# pierce-test-board.net
KiCad netlist of a schematic drawn in EAGLE
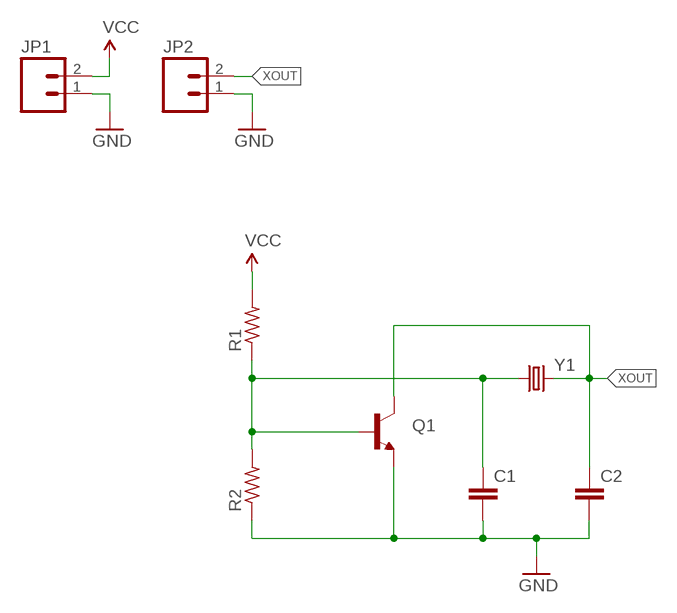
[diagram p0: schematic, sheet 1]

(export (version "E")
  (design (tool "Eeschema 10.0.6"))
  (components
    (comp (ref "C1")
      (value "CAPACITOR-CERAMIC025-024X044")
      (footprint "eagle-import:C025-024X044")
      (libsource (lib "eagle-import") (part "CAPACITOR-CERAMIC025-024X044"))
    )
    (comp (ref "C2")
      (value "CAPACITOR-CERAMIC025-024X044")
      (footprint "eagle-import:C025-024X044")
      (libsource (lib "eagle-import") (part "CAPACITOR-CERAMIC025-024X044"))
    )
    (comp (ref "JP1")
      (value "M02PTH")
      (footprint "eagle-import:1X02")
      (libsource (lib "eagle-import") (part "M02PTH"))
    )
    (comp (ref "JP2")
      (value "M02PTH")
      (footprint "eagle-import:1X02")
      (libsource (lib "eagle-import") (part "M02PTH"))
    )
    (comp (ref "Q1")
      (value "TRANSISTOR_NPNTO-92-AMMO-EBC")
      (footprint "eagle-import:TO-92-AMMO")
      (libsource (lib "eagle-import") (part "TRANSISTOR_NPNTO-92-AMMO-EBC"))
    )
    (comp (ref "R1")
      (value "RESISTORPTH-AXIAL-5.08MM")
      (footprint "eagle-import:RESISTOR-AXIAL-PTH-5.08MM")
      (libsource (lib "eagle-import") (part "RESISTORPTH-AXIAL-5.08MM"))
    )
    (comp (ref "R2")
      (value "RESISTORPTH-AXIAL-5.08MM")
      (footprint "eagle-import:RESISTOR-AXIAL-PTH-5.08MM")
      (libsource (lib "eagle-import") (part "RESISTORPTH-AXIAL-5.08MM"))
    )
    (comp (ref "Y1")
      (value "CRYSTALHC49UV")
      (footprint "eagle-import:HC49U-V")
      (libsource (lib "eagle-import") (part "CRYSTALHC49UV"))
    )
  )
  (nets
    (net (code "1") (name "GND") (class "Default")
      (node (ref "C1") (pin "2") (pinfunction "2_2") (pintype "passive"))
      (node (ref "C2") (pin "2") (pinfunction "2_2") (pintype "passive"))
      (node (ref "JP1") (pin "1") (pinfunction "1_1") (pintype "passive"))
      (node (ref "JP2") (pin "1") (pinfunction "1_1") (pintype "passive"))
      (node (ref "Q1") (pin "1") (pinfunction "E_1") (pintype "passive"))
      (node (ref "R2") (pin "P$1") (pinfunction "1_P$1") (pintype "passive"))
    )
    (net (code "2") (name "Net-(Q1-B)") (class "Default")
      (node (ref "C1") (pin "1") (pinfunction "1_1") (pintype "passive"))
      (node (ref "Q1") (pin "2") (pinfunction "B_2") (pintype "passive"))
      (node (ref "R1") (pin "P$1") (pinfunction "1_P$1") (pintype "passive"))
      (node (ref "R2") (pin "P$2") (pinfunction "2_P$2") (pintype "passive"))
      (node (ref "Y1") (pin "1") (pinfunction "1_1") (pintype "passive"))
    )
    (net (code "3") (name "VCC") (class "Default")
      (node (ref "JP1") (pin "2") (pinfunction "2_2") (pintype "passive"))
      (node (ref "R1") (pin "P$2") (pinfunction "2_P$2") (pintype "passive"))
    )
    (net (code "4") (name "XOUT") (class "Default")
      (node (ref "C2") (pin "1") (pinfunction "1_1") (pintype "passive"))
      (node (ref "JP2") (pin "2") (pinfunction "2_2") (pintype "passive"))
      (node (ref "Q1") (pin "3") (pinfunction "C_3") (pintype "passive"))
      (node (ref "Y1") (pin "2") (pinfunction "2_2") (pintype "passive"))
    )
  )
)
